# untitled.net
KiCad netlist of a schematic drawn in EAGLE
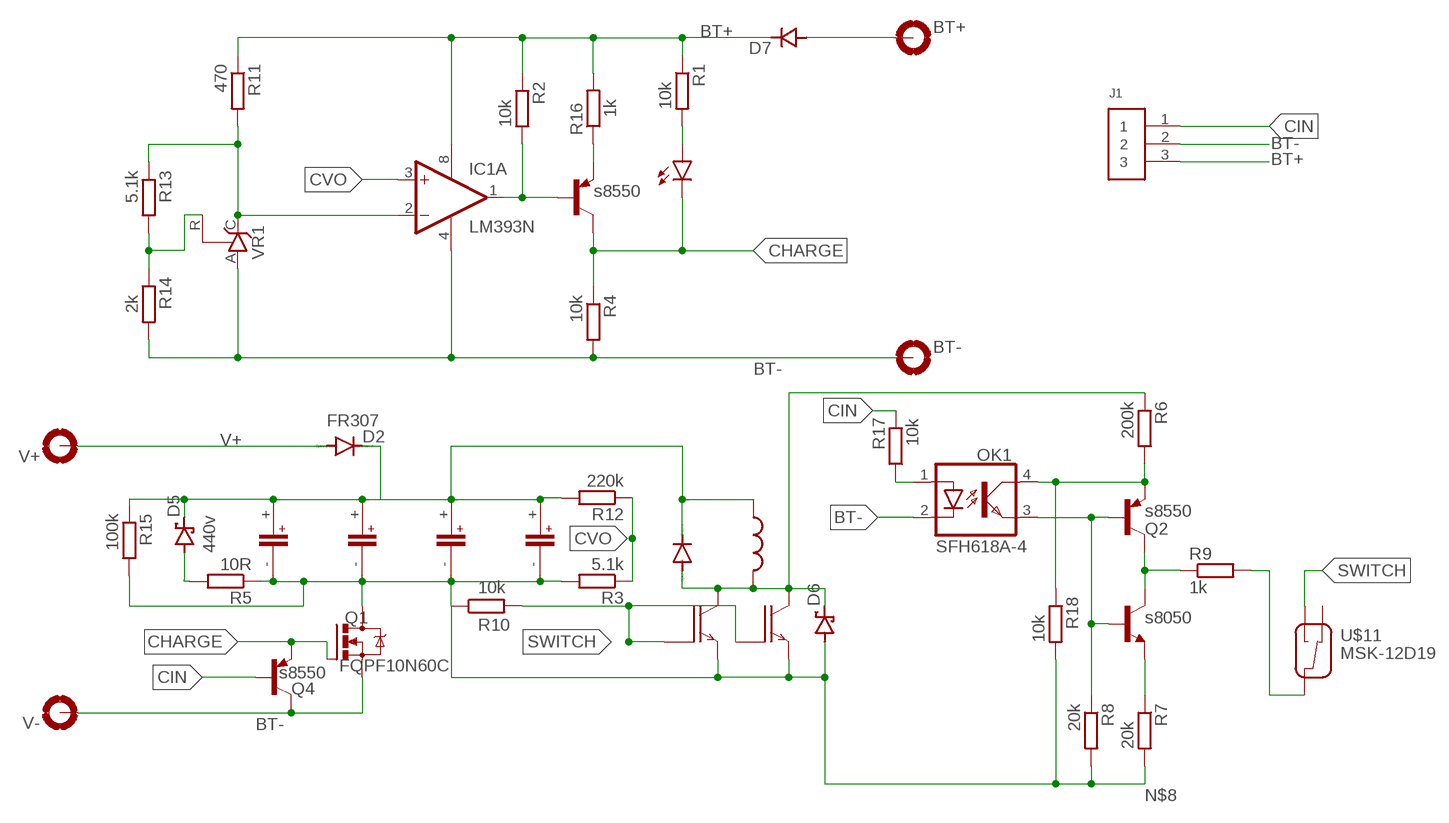
[diagram p0: schematic, sheet 1]

(export (version "E")
  (design (tool "Eeschema 10.0.6"))
  (components
    (comp (ref "BT+")
      (value "MOUNT-PAD-ROUND3.0")
      (footprint "eagle-import:3,0-PAD")
      (libsource (lib "eagle-import") (part "MOUNT-PAD-ROUND3.0"))
    )
    (comp (ref "BT-")
      (value "MOUNT-PAD-ROUND3.0")
      (footprint "eagle-import:3,0-PAD")
      (libsource (lib "eagle-import") (part "MOUNT-PAD-ROUND3.0"))
    )
    (comp (ref "D1")
      (value "SB320")
      (footprint "eagle-import:DO201-15")
      (libsource (lib "eagle-import") (part "SB320"))
    )
    (comp (ref "D2")
      (value "FR307")
      (footprint "eagle-import:DO15-12")
      (libsource (lib "eagle-import") (part "1N5060GP"))
    )
    (comp (ref "D5")
      (value "440v")
      (footprint "eagle-import:E2LINE")
      (libsource (lib "eagle-import") (part "DS_E2L"))
    )
    (comp (ref "D6")
      (value "DS_E2L")
      (footprint "eagle-import:E2LINE")
      (libsource (lib "eagle-import") (part "DS_E2L"))
    )
    (comp (ref "D7")
      (value "D_E2L")
      (footprint "eagle-import:E2LINE")
      (libsource (lib "eagle-import") (part "D_E2L"))
    )
    (comp (ref "IC1")
      (value "LM393N")
      (footprint "eagle-import:DIL08")
      (libsource (lib "eagle-import") (part "LM393N"))
    )
    (comp (ref "J1")
      (value "61300311121")
      (footprint "eagle-import:61300311121")
      (fields
        (field (name "DIGI_KEY_PART_NUMBER") "732-5316-ND")
        (field (name "MANUFACTURER") "Wurth Electronics Inc.")
        (field (name "CREATED_BY") "PCBLayout.com")
      )
      (libsource (lib "eagle-import") (part "61300311121"))
    )
    (comp (ref "LED1")
      (value "TLLY4400")
      (footprint "eagle-import:LED3MM")
      (fields (field (name "MF") "VISHAY SEMICONDUCTOR"))
      (libsource (lib "eagle-import") (part "TLLY4400"))
    )
    (comp (ref "OK1")
      (value "SFH618A-4")
      (footprint "eagle-import:DIP4")
      (fields (field (name "MF") "VISHAY/TELEFUNKEN"))
      (libsource (lib "eagle-import") (part "SFH618?A-4"))
    )
    (comp (ref "Q1")
      (value "FQPF10N60C")
      (footprint "eagle-import:TO220BV")
      (libsource (lib "eagle-import") (part "IRF740"))
    )
    (comp (ref "Q2")
      (value "s8550")
      (footprint "eagle-import:TO92")
      (libsource (lib "eagle-import") (part "2N3906"))
    )
    (comp (ref "Q3")
      (value "s8550")
      (footprint "eagle-import:TO92")
      (libsource (lib "eagle-import") (part "2N3906"))
    )
    (comp (ref "Q4")
      (value "s8550")
      (footprint "eagle-import:TO92")
      (libsource (lib "eagle-import") (part "2N3906"))
    )
    (comp (ref "R1")
      (value "10k")
      (footprint "eagle-import:0207_2V")
      (libsource (lib "eagle-import") (part "R-EU_0207/2V"))
    )
    (comp (ref "R2")
      (value "10k")
      (footprint "eagle-import:0207_2V")
      (libsource (lib "eagle-import") (part "R-EU_0207/2V"))
    )
    (comp (ref "R3")
      (value "5.1k")
      (footprint "eagle-import:0207_2V")
      (libsource (lib "eagle-import") (part "R-EU_0207/2V"))
    )
    (comp (ref "R4")
      (value "10k")
      (footprint "eagle-import:0207_2V")
      (libsource (lib "eagle-import") (part "R-EU_0207/2V"))
    )
    (comp (ref "R5")
      (value "10R")
      (footprint "eagle-import:0207_2V")
      (libsource (lib "eagle-import") (part "R-EU_0207/2V"))
    )
    (comp (ref "R6")
      (value "200k")
      (footprint "eagle-import:0207_2V")
      (libsource (lib "eagle-import") (part "R-EU_0207/2V"))
    )
    (comp (ref "R7")
      (value "20k")
      (footprint "eagle-import:0207_2V")
      (libsource (lib "eagle-import") (part "R-EU_0207/2V"))
    )
    (comp (ref "R8")
      (value "20k")
      (footprint "eagle-import:0207_2V")
      (libsource (lib "eagle-import") (part "R-EU_0207/2V"))
    )
    (comp (ref "R9")
      (value "1k")
      (footprint "eagle-import:0309_12")
      (libsource (lib "eagle-import") (part "R-EU_0309/12"))
    )
    (comp (ref "R10")
      (value "10k")
      (footprint "eagle-import:0207_2V")
      (libsource (lib "eagle-import") (part "R-EU_0207/2V"))
    )
    (comp (ref "R11")
      (value "470")
      (footprint "eagle-import:0207_2V")
      (libsource (lib "eagle-import") (part "R-EU_0207/2V"))
    )
    (comp (ref "R12")
      (value "220k")
      (footprint "eagle-import:0207_2V")
      (libsource (lib "eagle-import") (part "R-EU_0207/2V"))
    )
    (comp (ref "R13")
      (value "5.1k")
      (footprint "eagle-import:0207_2V")
      (libsource (lib "eagle-import") (part "R-EU_0207/2V"))
    )
    (comp (ref "R14")
      (value "2k")
      (footprint "eagle-import:0207_2V")
      (libsource (lib "eagle-import") (part "R-EU_0207/2V"))
    )
    (comp (ref "R15")
      (value "100k")
      (footprint "eagle-import:0207_2V")
      (libsource (lib "eagle-import") (part "R-EU_0207/2V"))
    )
    (comp (ref "R16")
      (value "1k")
      (footprint "eagle-import:0207_2V")
      (libsource (lib "eagle-import") (part "R-EU_0207/2V"))
    )
    (comp (ref "R17")
      (value "10k")
      (footprint "eagle-import:0207_2V")
      (libsource (lib "eagle-import") (part "R-EU_0207/2V"))
    )
    (comp (ref "R18")
      (value "10k")
      (footprint "eagle-import:0207_2V")
      (libsource (lib "eagle-import") (part "R-EU_0207/2V"))
    )
    (comp (ref "T3")
      (value "s8050")
      (footprint "eagle-import:TO92")
      (libsource (lib "eagle-import") (part "2N3704"))
    )
    (comp (ref "U$1")
      (value "RUBYCON_450V_270UF")
      (footprint "eagle-import:RUBYCON_22_40")
      (libsource (lib "eagle-import") (part "RUBYCON_450V_270UF"))
    )
    (comp (ref "U$2")
      (value "RUBYCON_450V_270UF")
      (footprint "eagle-import:RUBYCON_22_40")
      (libsource (lib "eagle-import") (part "RUBYCON_450V_270UF"))
    )
    (comp (ref "U$3")
      (value "RUBYCON_450V_270UF")
      (footprint "eagle-import:RUBYCON_22_40")
      (libsource (lib "eagle-import") (part "RUBYCON_450V_270UF"))
    )
    (comp (ref "U$4")
      (value "RUBYCON_450V_270UF")
      (footprint "eagle-import:RUBYCON_22_40")
      (libsource (lib "eagle-import") (part "RUBYCON_450V_270UF"))
    )
    (comp (ref "U$6")
      (value "COIL-301025")
      (footprint "eagle-import:30_10_25")
      (libsource (lib "eagle-import") (part "COIL-301025"))
    )
    (comp (ref "U$9")
      (value "IGBT-N-TO247")
      (footprint "eagle-import:TO-247AD-V")
      (libsource (lib "eagle-import") (part "IGBT-N-TO247"))
    )
    (comp (ref "U$11")
      (value "MSK-12D19")
      (footprint "eagle-import:12D19")
      (libsource (lib "eagle-import") (part "MSK-12D19"))
    )
    (comp (ref "U$13")
      (value "IGBT-N-TO247")
      (footprint "eagle-import:TO-247AD-V")
      (libsource (lib "eagle-import") (part "IGBT-N-TO247"))
    )
    (comp (ref "V+")
      (value "MOUNT-PAD-ROUND3.0")
      (footprint "eagle-import:3,0-PAD")
      (libsource (lib "eagle-import") (part "MOUNT-PAD-ROUND3.0"))
    )
    (comp (ref "V-")
      (value "MOUNT-PAD-ROUND3.0")
      (footprint "eagle-import:3,0-PAD")
      (libsource (lib "eagle-import") (part "MOUNT-PAD-ROUND3.0"))
    )
    (comp (ref "VR1")
      (value "TL431CLP")
      (footprint "eagle-import:TO92-CLP")
      (libsource (lib "eagle-import") (part "TL431CLP"))
    )
  )
  (nets
    (net (code "1") (name "/BT+") (class "Default")
      (node (ref "D7") (pin "1") (pinfunction "C_1") (pintype "passive"))
      (node (ref "IC1") (pin "8") (pinfunction "V+_8") (pintype "power_in"))
      (node (ref "J1") (pin "3") (pinfunction "3_3") (pintype "passive"))
      (node (ref "R1") (pin "1") (pinfunction "1_1") (pintype "passive"))
      (node (ref "R11") (pin "1") (pinfunction "1_1") (pintype "passive"))
      (node (ref "R16") (pin "2") (pinfunction "2_2") (pintype "passive"))
      (node (ref "R2") (pin "1") (pinfunction "1_1") (pintype "passive"))
    )
    (net (code "2") (name "/N$8") (class "Default")
      (node (ref "D6") (pin "2") (pinfunction "A_2") (pintype "passive"))
      (node (ref "Q1") (pin "D") (pinfunction "D_D") (pintype "passive"))
      (node (ref "R10") (pin "1") (pinfunction "1_1") (pintype "passive"))
      (node (ref "R15") (pin "2") (pinfunction "2_2") (pintype "passive"))
      (node (ref "R18") (pin "2") (pinfunction "2_2") (pintype "passive"))
      (node (ref "R3") (pin "2") (pinfunction "2_2") (pintype "passive"))
      (node (ref "R5") (pin "1") (pinfunction "1_1") (pintype "passive"))
      (node (ref "R7") (pin "2") (pinfunction "2_2") (pintype "passive"))
      (node (ref "R8") (pin "2") (pinfunction "2_2") (pintype "passive"))
      (node (ref "U$1") (pin "-") (pinfunction "-_-") (pintype "bidirectional"))
      (node (ref "U$13") (pin "E") (pinfunction "E_E") (pintype "passive"))
      (node (ref "U$2") (pin "-") (pinfunction "-_-") (pintype "bidirectional"))
      (node (ref "U$3") (pin "-") (pinfunction "-_-") (pintype "bidirectional"))
      (node (ref "U$4") (pin "-") (pinfunction "-_-") (pintype "bidirectional"))
      (node (ref "U$9") (pin "E") (pinfunction "E_E") (pintype "passive"))
    )
    (net (code "3") (name "/V+") (class "Default")
      (node (ref "D2") (pin "A") (pinfunction "A_A") (pintype "passive"))
      (node (ref "V+") (pin "B3,0") (pinfunction "MOUNT_B3,0") (pintype "passive"))
    )
    (net (code "4") (name "BT-") (class "Default")
      (node (ref "BT-") (pin "B3,0") (pinfunction "MOUNT_B3,0") (pintype "passive"))
      (node (ref "IC1") (pin "4") (pinfunction "V-_4") (pintype "power_in"))
      (node (ref "J1") (pin "2") (pinfunction "2_2") (pintype "passive"))
      (node (ref "OK1") (pin "2") (pinfunction "C_2") (pintype "passive"))
      (node (ref "Q1") (pin "S") (pinfunction "S_S") (pintype "passive"))
      (node (ref "Q4") (pin "1") (pinfunction "C_1") (pintype "passive"))
      (node (ref "R14") (pin "2") (pinfunction "2_2") (pintype "passive"))
      (node (ref "R4") (pin "2") (pinfunction "2_2") (pintype "passive"))
      (node (ref "V-") (pin "B3,0") (pinfunction "MOUNT_B3,0") (pintype "passive"))
      (node (ref "VR1") (pin "A") (pinfunction "A_A") (pintype "passive"))
    )
    (net (code "5") (name "CHARGE") (class "Default")
      (node (ref "LED1") (pin "K") (pinfunction "C_K") (pintype "passive"))
      (node (ref "Q1") (pin "G") (pinfunction "G_G") (pintype "passive"))
      (node (ref "Q3") (pin "1") (pinfunction "C_1") (pintype "passive"))
      (node (ref "Q4") (pin "3") (pinfunction "E_3") (pintype "passive"))
      (node (ref "R4") (pin "1") (pinfunction "1_1") (pintype "passive"))
    )
    (net (code "6") (name "CIN") (class "Default")
      (node (ref "J1") (pin "1") (pinfunction "1_1") (pintype "passive"))
      (node (ref "Q4") (pin "2") (pinfunction "B_2") (pintype "passive"))
      (node (ref "R17") (pin "2") (pinfunction "2_2") (pintype "passive"))
    )
    (net (code "7") (name "CVO") (class "Default")
      (node (ref "IC1") (pin "3") (pinfunction "+IN_3") (pintype "input"))
      (node (ref "R12") (pin "1") (pinfunction "1_1") (pintype "passive"))
      (node (ref "R3") (pin "1") (pinfunction "1_1") (pintype "passive"))
    )
    (net (code "8") (name "Net-(BT+-MOUNT)") (class "Default")
      (node (ref "BT+") (pin "B3,0") (pinfunction "MOUNT_B3,0") (pintype "passive"))
      (node (ref "D7") (pin "2") (pinfunction "A_2") (pintype "passive"))
    )
    (net (code "9") (name "Net-(D5-A)") (class "Default")
      (node (ref "D5") (pin "2") (pinfunction "A_2") (pintype "passive"))
      (node (ref "R5") (pin "2") (pinfunction "2_2") (pintype "passive"))
    )
    (net (code "10") (name "Net-(D5-K)") (class "Default")
      (node (ref "D1") (pin "C") (pinfunction "C_C") (pintype "passive"))
      (node (ref "D2") (pin "C") (pinfunction "C_C") (pintype "passive"))
      (node (ref "D5") (pin "1") (pinfunction "K_1") (pintype "passive"))
      (node (ref "R12") (pin "2") (pinfunction "2_2") (pintype "passive"))
      (node (ref "R15") (pin "1") (pinfunction "1_1") (pintype "passive"))
      (node (ref "U$1") (pin "+") (pinfunction "+_+") (pintype "bidirectional"))
      (node (ref "U$2") (pin "+") (pinfunction "+_+") (pintype "bidirectional"))
      (node (ref "U$3") (pin "+") (pinfunction "+_+") (pintype "bidirectional"))
      (node (ref "U$4") (pin "+") (pinfunction "+_+") (pintype "bidirectional"))
      (node (ref "U$6") (pin "P$1") (pinfunction "1_P$1") (pintype "passive"))
    )
    (net (code "11") (name "Net-(D6-K)") (class "Default")
      (node (ref "D1") (pin "A") (pinfunction "A_A") (pintype "passive"))
      (node (ref "D6") (pin "1") (pinfunction "K_1") (pintype "passive"))
      (node (ref "R6") (pin "1") (pinfunction "1_1") (pintype "passive"))
      (node (ref "U$13") (pin "C") (pinfunction "C_C") (pintype "passive"))
      (node (ref "U$6") (pin "P$2") (pinfunction "2_P$2") (pintype "passive"))
      (node (ref "U$9") (pin "C") (pinfunction "C_C") (pintype "passive"))
    )
    (net (code "12") (name "Net-(IC1A--IN)") (class "Default")
      (node (ref "IC1") (pin "2") (pinfunction "-IN_2") (pintype "input"))
      (node (ref "R11") (pin "2") (pinfunction "2_2") (pintype "passive"))
      (node (ref "R13") (pin "1") (pinfunction "1_1") (pintype "passive"))
      (node (ref "VR1") (pin "C") (pinfunction "C_C") (pintype "passive"))
    )
    (net (code "13") (name "Net-(IC1A-OUT)") (class "Default")
      (node (ref "IC1") (pin "1") (pinfunction "OUT_1") (pintype "output"))
      (node (ref "Q3") (pin "2") (pinfunction "B_2") (pintype "passive"))
      (node (ref "R2") (pin "2") (pinfunction "2_2") (pintype "passive"))
    )
    (net (code "14") (name "Net-(LED1-PadA)") (class "Default")
      (node (ref "LED1") (pin "A") (pinfunction "A_A") (pintype "passive"))
      (node (ref "R1") (pin "2") (pinfunction "2_2") (pintype "passive"))
    )
    (net (code "15") (name "Net-(OK1-A)") (class "Default")
      (node (ref "OK1") (pin "1") (pinfunction "A_1") (pintype "passive"))
      (node (ref "R17") (pin "1") (pinfunction "1_1") (pintype "passive"))
    )
    (net (code "16") (name "Net-(OK1-COL)") (class "Default")
      (node (ref "OK1") (pin "4") (pinfunction "COL_4") (pintype "passive"))
      (node (ref "Q2") (pin "3") (pinfunction "E_3") (pintype "passive"))
      (node (ref "R18") (pin "1") (pinfunction "1_1") (pintype "passive"))
      (node (ref "R6") (pin "2") (pinfunction "2_2") (pintype "passive"))
    )
    (net (code "17") (name "Net-(OK1-EMIT)") (class "Default")
      (node (ref "OK1") (pin "3") (pinfunction "EMIT_3") (pintype "passive"))
      (node (ref "Q2") (pin "2") (pinfunction "B_2") (pintype "passive"))
      (node (ref "R8") (pin "1") (pinfunction "1_1") (pintype "passive"))
      (node (ref "T3") (pin "1") (pinfunction "B_1") (pintype "passive"))
    )
    (net (code "18") (name "Net-(Q2-C)") (class "Default")
      (node (ref "Q2") (pin "1") (pinfunction "C_1") (pintype "passive"))
      (node (ref "R9") (pin "1") (pinfunction "1_1") (pintype "passive"))
      (node (ref "T3") (pin "2") (pinfunction "C_2") (pintype "passive"))
    )
    (net (code "19") (name "Net-(Q3-E)") (class "Default")
      (node (ref "Q3") (pin "3") (pinfunction "E_3") (pintype "passive"))
      (node (ref "R16") (pin "1") (pinfunction "1_1") (pintype "passive"))
    )
    (net (code "20") (name "Net-(R9-Pad2)") (class "Default")
      (node (ref "R9") (pin "2") (pinfunction "2_2") (pintype "passive"))
      (node (ref "U$11") (pin "COM") (pinfunction "COM_COM") (pintype "passive"))
    )
    (net (code "21") (name "Net-(R13-Pad2)") (class "Default")
      (node (ref "R13") (pin "2") (pinfunction "2_2") (pintype "passive"))
      (node (ref "R14") (pin "1") (pinfunction "1_1") (pintype "passive"))
      (node (ref "VR1") (pin "R") (pinfunction "R_R") (pintype "passive"))
    )
    (net (code "22") (name "Net-(T3-E)") (class "Default")
      (node (ref "R7") (pin "1") (pinfunction "1_1") (pintype "passive"))
      (node (ref "T3") (pin "3") (pinfunction "E_3") (pintype "passive"))
    )
    (net (code "23") (name "SWITCH") (class "Default")
      (node (ref "R10") (pin "2") (pinfunction "2_2") (pintype "passive"))
      (node (ref "U$11") (pin "NO") (pinfunction "NO_NO") (pintype "passive"))
      (node (ref "U$13") (pin "G") (pinfunction "G_G") (pintype "passive"))
      (node (ref "U$9") (pin "G") (pinfunction "G_G") (pintype "passive"))
    )
    (net (code "24") (name "unconnected-(U$11-PadNC)") (class "Default")
      (node (ref "U$11") (pin "NC") (pinfunction "NC_NC") (pintype "passive"))
    )
  )
)
